# Altium_ir-rgb-controller-schematic.net
KiCad netlist of a schematic drawn in Altium Designer
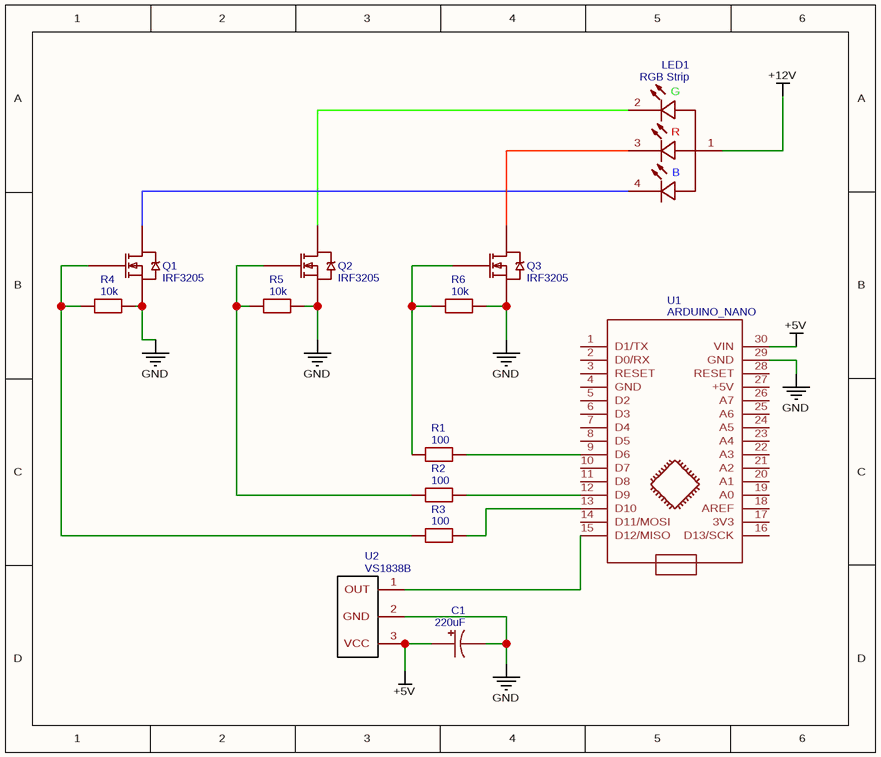
[diagram p0: [Altium] ir-rgb-controller-schematic.schdoc]

(export (version "E")
  (design (tool "Eeschema 10.0.6"))
  (components
    (comp (ref "C1")
      (value "220uF")
      (fields (field (name "BOM_SUPPLIER PART") "C165659") (field (name "CONTRIBUTOR") "LCSC"))
      (libsource (lib "altium-import") (part "root_3_220uF_"))
    )
    (comp (ref "LED1")
      (value "RGB Strip")
      (fields (field (name "CONTRIBUTOR") "LCSC"))
      (libsource (lib "altium-import") (part "root_0_RGB Strip_"))
    )
    (comp (ref "Q1")
      (value "IRF3205")
      (description "HEXFET Power MOSFET")
      (libsource (lib "altium-import") (part "root_0_IRF3205_"))
    )
    (comp (ref "Q2")
      (value "IRF3205")
      (description "HEXFET Power MOSFET")
      (libsource (lib "altium-import") (part "root_0_IRF3205_"))
    )
    (comp (ref "Q3")
      (value "IRF3205")
      (description "HEXFET Power MOSFET")
      (libsource (lib "altium-import") (part "root_0_IRF3205_"))
    )
    (comp (ref "R1")
      (value "100")
      (fields (field (name "CONTRIBUTOR") "LCEDA_Lib"))
      (libsource (lib "altium-import") (part "root_0_100_"))
    )
    (comp (ref "R2")
      (value "100")
      (fields (field (name "CONTRIBUTOR") "LCEDA_Lib"))
      (libsource (lib "altium-import") (part "root_0_100_"))
    )
    (comp (ref "R3")
      (value "100")
      (fields (field (name "CONTRIBUTOR") "LCEDA_Lib"))
      (libsource (lib "altium-import") (part "root_0_100_"))
    )
    (comp (ref "R4")
      (value "10k")
      (fields (field (name "CONTRIBUTOR") "LCEDA_Lib"))
      (libsource (lib "altium-import") (part "root_0_10k_"))
    )
    (comp (ref "R5")
      (value "10k")
      (fields (field (name "CONTRIBUTOR") "LCEDA_Lib"))
      (libsource (lib "altium-import") (part "root_0_10k_"))
    )
    (comp (ref "R6")
      (value "10k")
      (fields (field (name "CONTRIBUTOR") "LCEDA_Lib"))
      (libsource (lib "altium-import") (part "root_0_10k_"))
    )
    (comp (ref "U1") (value "ARDUINO_NANO") (libsource (lib "altium-import") (part "root_0_ARDUINO_NANO_")))
    (comp (ref "U2")
      (value "VS1838B")
      (fields (field (name "CONTRIBUTOR") "franx411"))
      (libsource (lib "altium-import") (part "root_3_VS1838B_"))
    )
  )
  (nets
    (net (code "1") (name "+5V") (class "Default")
      (node (ref "C1") (pin "1") (pinfunction "1_1") (pintype "passive"))
      (node (ref "U1") (pin "30") (pinfunction "VIN_30") (pintype "passive"))
      (node (ref "U2") (pin "3") (pinfunction "VCC_3") (pintype "passive"))
    )
    (net (code "2") (name "+12V") (class "Default")
      (node (ref "LED1") (pin "1") (pinfunction "CA_1") (pintype "passive"))
    )
    (net (code "3") (name "GND") (class "Default")
      (node (ref "C1") (pin "2") (pinfunction "2_2") (pintype "passive"))
      (node (ref "Q1") (pin "3") (pinfunction "S_3") (pintype "passive"))
      (node (ref "Q2") (pin "3") (pinfunction "S_3") (pintype "passive"))
      (node (ref "Q3") (pin "3") (pinfunction "S_3") (pintype "passive"))
      (node (ref "R4") (pin "2") (pinfunction "2_2") (pintype "passive"))
      (node (ref "R5") (pin "2") (pinfunction "2_2") (pintype "passive"))
      (node (ref "R6") (pin "2") (pinfunction "2_2") (pintype "passive"))
      (node (ref "U1") (pin "29") (pinfunction "GND_29") (pintype "passive"))
      (node (ref "U2") (pin "2") (pinfunction "GND_2") (pintype "passive"))
    )
    (net (code "4") (name "Net-(LED1-KB)") (class "Default")
      (node (ref "LED1") (pin "4") (pinfunction "KB_4") (pintype "passive"))
      (node (ref "Q1") (pin "2") (pinfunction "D_2") (pintype "passive"))
    )
    (net (code "5") (name "Net-(LED1-KG)") (class "Default")
      (node (ref "LED1") (pin "2") (pinfunction "KG_2") (pintype "passive"))
      (node (ref "Q2") (pin "2") (pinfunction "D_2") (pintype "passive"))
    )
    (net (code "6") (name "Net-(LED1-KR)") (class "Default")
      (node (ref "LED1") (pin "3") (pinfunction "KR_3") (pintype "passive"))
      (node (ref "Q3") (pin "2") (pinfunction "D_2") (pintype "passive"))
    )
    (net (code "7") (name "Net-(Q1-G)") (class "Default")
      (node (ref "Q1") (pin "1") (pinfunction "G_1") (pintype "passive"))
      (node (ref "R3") (pin "1") (pinfunction "1_1") (pintype "passive"))
      (node (ref "R4") (pin "1") (pinfunction "1_1") (pintype "passive"))
    )
    (net (code "8") (name "Net-(Q2-G)") (class "Default")
      (node (ref "Q2") (pin "1") (pinfunction "G_1") (pintype "passive"))
      (node (ref "R2") (pin "1") (pinfunction "1_1") (pintype "passive"))
      (node (ref "R5") (pin "1") (pinfunction "1_1") (pintype "passive"))
    )
    (net (code "9") (name "Net-(Q3-G)") (class "Default")
      (node (ref "Q3") (pin "1") (pinfunction "G_1") (pintype "passive"))
      (node (ref "R1") (pin "1") (pinfunction "1_1") (pintype "passive"))
      (node (ref "R6") (pin "1") (pinfunction "1_1") (pintype "passive"))
    )
    (net (code "10") (name "Net-(U1-D6)") (class "Default")
      (node (ref "R1") (pin "2") (pinfunction "2_2") (pintype "passive"))
      (node (ref "U1") (pin "9") (pinfunction "D6_9") (pintype "passive"))
    )
    (net (code "11") (name "Net-(U1-D9)") (class "Default")
      (node (ref "R2") (pin "2") (pinfunction "2_2") (pintype "passive"))
      (node (ref "U1") (pin "12") (pinfunction "D9_12") (pintype "passive"))
    )
    (net (code "12") (name "Net-(U1-D10)") (class "Default")
      (node (ref "R3") (pin "2") (pinfunction "2_2") (pintype "passive"))
      (node (ref "U1") (pin "13") (pinfunction "D10_13") (pintype "passive"))
    )
    (net (code "13") (name "Net-(U1-D12{slash}MISO)") (class "Default")
      (node (ref "U1") (pin "15") (pinfunction "D12/MISO_15") (pintype "passive"))
      (node (ref "U2") (pin "1") (pinfunction "OUT_1") (pintype "passive"))
    )
    (net (code "14") (name "unconnected-(U1-+5V-Pad27)") (class "Default")
      (node (ref "U1") (pin "27") (pinfunction "+5V_27") (pintype "passive"))
    )
    (net (code "15") (name "unconnected-(U1-3V3-Pad17)") (class "Default")
      (node (ref "U1") (pin "17") (pinfunction "3V3_17") (pintype "passive"))
    )
    (net (code "16") (name "unconnected-(U1-A0-Pad19)") (class "Default")
      (node (ref "U1") (pin "19") (pinfunction "A0_19") (pintype "passive"))
    )
    (net (code "17") (name "unconnected-(U1-A1-Pad20)") (class "Default")
      (node (ref "U1") (pin "20") (pinfunction "A1_20") (pintype "passive"))
    )
    (net (code "18") (name "unconnected-(U1-A2-Pad21)") (class "Default")
      (node (ref "U1") (pin "21") (pinfunction "A2_21") (pintype "passive"))
    )
    (net (code "19") (name "unconnected-(U1-A3-Pad22)") (class "Default")
      (node (ref "U1") (pin "22") (pinfunction "A3_22") (pintype "passive"))
    )
    (net (code "20") (name "unconnected-(U1-A4-Pad23)") (class "Default")
      (node (ref "U1") (pin "23") (pinfunction "A4_23") (pintype "passive"))
    )
    (net (code "21") (name "unconnected-(U1-A5-Pad24)") (class "Default")
      (node (ref "U1") (pin "24") (pinfunction "A5_24") (pintype "passive"))
    )
    (net (code "22") (name "unconnected-(U1-A6-Pad25)") (class "Default")
      (node (ref "U1") (pin "25") (pinfunction "A6_25") (pintype "passive"))
    )
    (net (code "23") (name "unconnected-(U1-A7-Pad26)") (class "Default")
      (node (ref "U1") (pin "26") (pinfunction "A7_26") (pintype "passive"))
    )
    (net (code "24") (name "unconnected-(U1-AREF-Pad18)") (class "Default")
      (node (ref "U1") (pin "18") (pinfunction "AREF_18") (pintype "passive"))
    )
    (net (code "25") (name "unconnected-(U1-D0{slash}RX-Pad2)") (class "Default")
      (node (ref "U1") (pin "2") (pinfunction "D0/RX_2") (pintype "passive"))
    )
    (net (code "26") (name "unconnected-(U1-D1{slash}TX-Pad1)") (class "Default")
      (node (ref "U1") (pin "1") (pinfunction "D1/TX_1") (pintype "passive"))
    )
    (net (code "27") (name "unconnected-(U1-D2-Pad5)") (class "Default")
      (node (ref "U1") (pin "5") (pinfunction "D2_5") (pintype "passive"))
    )
    (net (code "28") (name "unconnected-(U1-D3-Pad6)") (class "Default")
      (node (ref "U1") (pin "6") (pinfunction "D3_6") (pintype "passive"))
    )
    (net (code "29") (name "unconnected-(U1-D4-Pad7)") (class "Default")
      (node (ref "U1") (pin "7") (pinfunction "D4_7") (pintype "passive"))
    )
    (net (code "30") (name "unconnected-(U1-D5-Pad8)") (class "Default")
      (node (ref "U1") (pin "8") (pinfunction "D5_8") (pintype "passive"))
    )
    (net (code "31") (name "unconnected-(U1-D7-Pad10)") (class "Default")
      (node (ref "U1") (pin "10") (pinfunction "D7_10") (pintype "passive"))
    )
    (net (code "32") (name "unconnected-(U1-D8-Pad11)") (class "Default")
      (node (ref "U1") (pin "11") (pinfunction "D8_11") (pintype "passive"))
    )
    (net (code "33") (name "unconnected-(U1-D11{slash}MOSI-Pad14)") (class "Default")
      (node (ref "U1") (pin "14") (pinfunction "D11/MOSI_14") (pintype "passive"))
    )
    (net (code "34") (name "unconnected-(U1-D13{slash}SCK-Pad16)") (class "Default")
      (node (ref "U1") (pin "16") (pinfunction "D13/SCK_16") (pintype "passive"))
    )
    (net (code "35") (name "unconnected-(U1-GND-Pad4)") (class "Default")
      (node (ref "U1") (pin "4") (pinfunction "GND_4") (pintype "passive"))
    )
    (net (code "36") (name "unconnected-(U1-RESET-Pad3)") (class "Default")
      (node (ref "U1") (pin "3") (pinfunction "RESET_3") (pintype "passive"))
    )
    (net (code "37") (name "unconnected-(U1-RESET-Pad28)") (class "Default")
      (node (ref "U1") (pin "28") (pinfunction "RESET_28") (pintype "passive"))
    )
  )
)
